# weichen-a-4.net
KiCad netlist of a schematic drawn in EAGLE
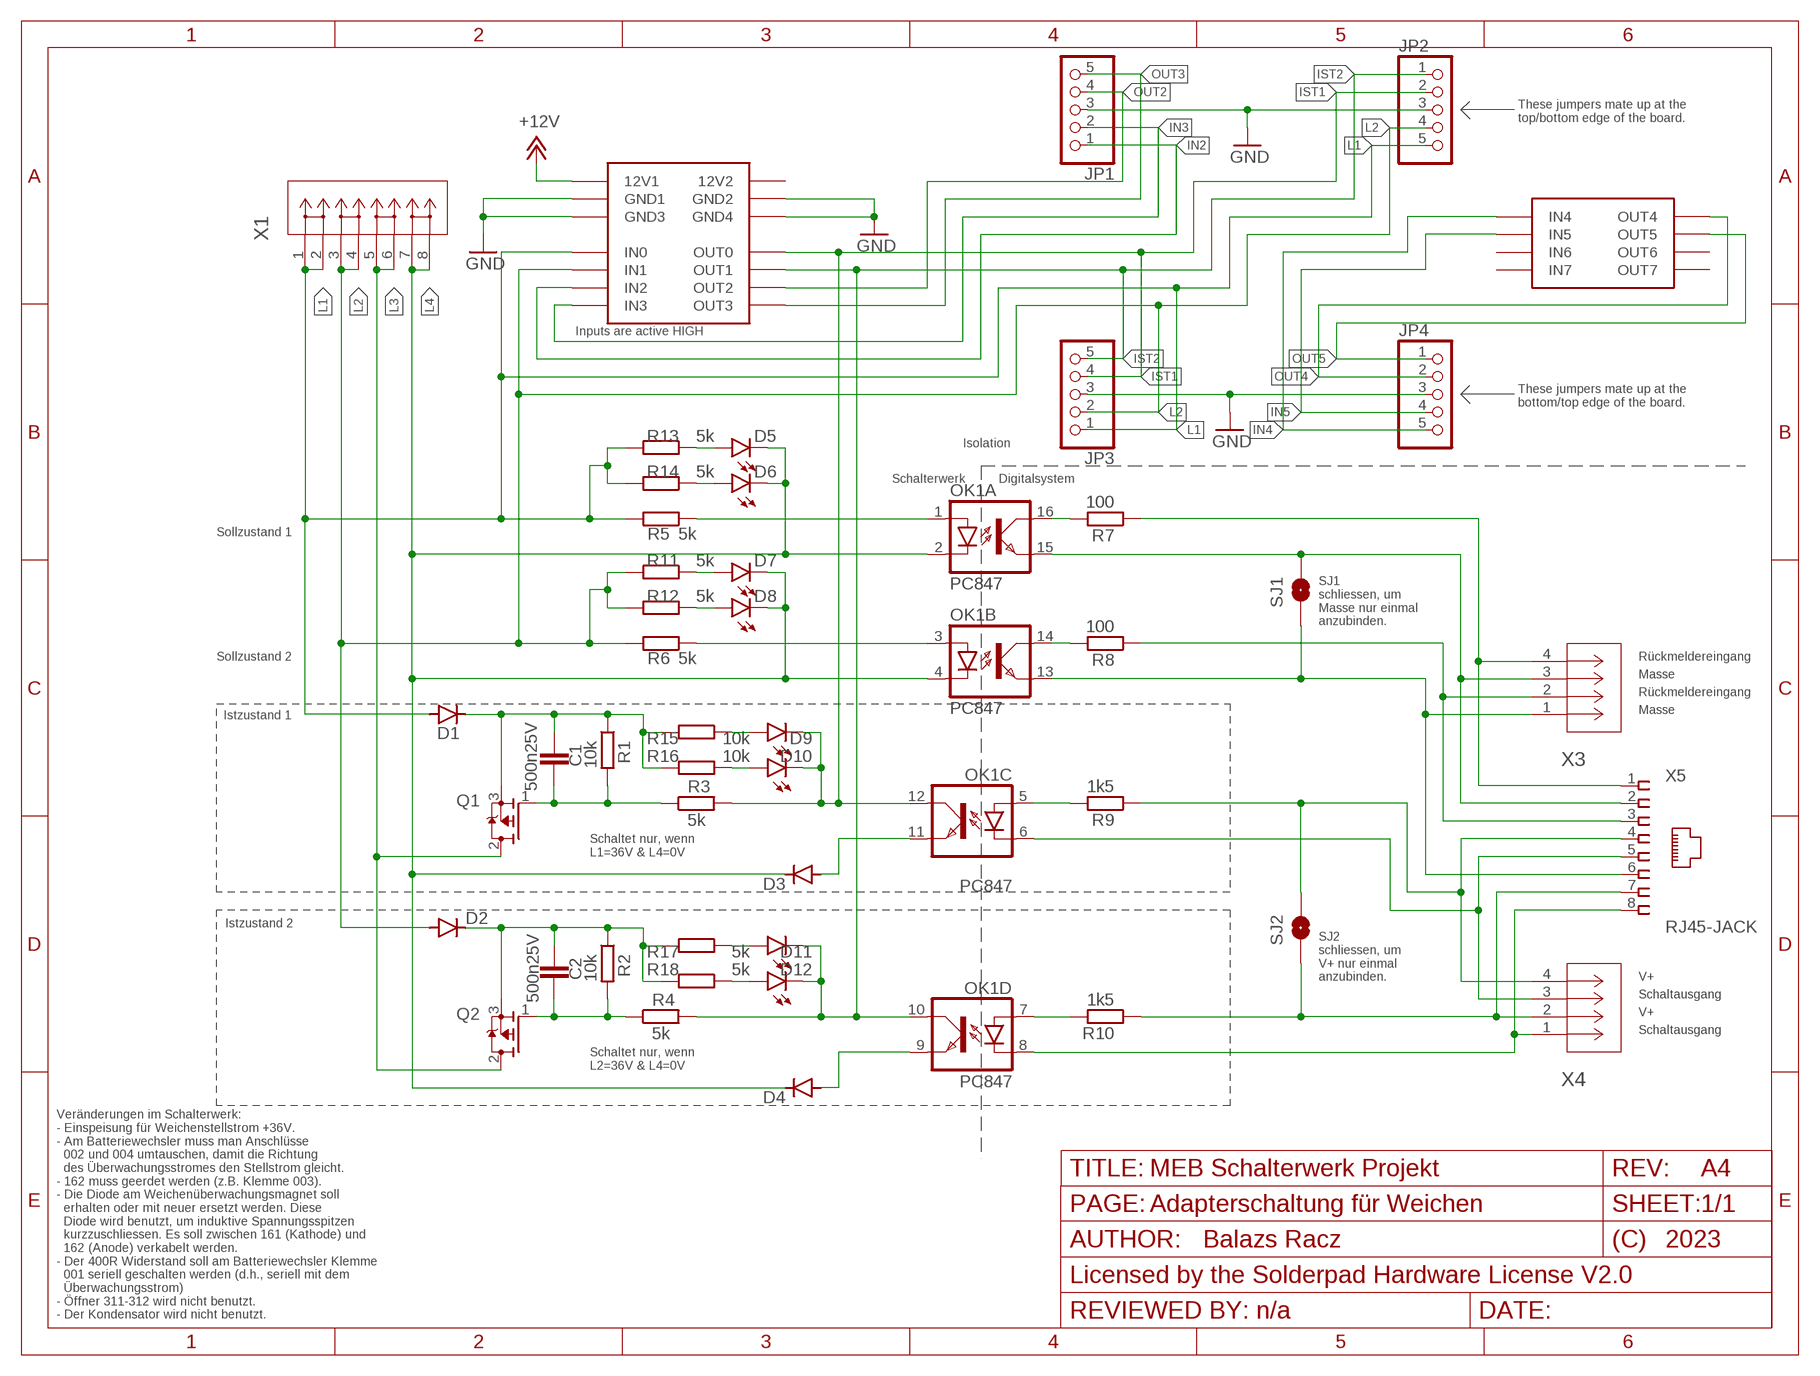
[diagram p0: schematic, sheet 1]

(export (version "E")
  (design (tool "Eeschema 10.0.6"))
  (components
    (comp (ref "C1")
      (value "500n25V")
      (footprint "eagle-import:C0805")
      (libsource (lib "eagle-import") (part "C-EUC0805"))
    )
    (comp (ref "C2")
      (value "500n25V")
      (footprint "eagle-import:C0805")
      (libsource (lib "eagle-import") (part "C-EUC0805"))
    )
    (comp (ref "D1")
      (value "DIODE-DO214AC")
      (footprint "eagle-import:DO214AC")
      (libsource (lib "eagle-import") (part "DIODE-DO214AC"))
    )
    (comp (ref "D2")
      (value "DIODE-DO214AC")
      (footprint "eagle-import:DO214AC")
      (libsource (lib "eagle-import") (part "DIODE-DO214AC"))
    )
    (comp (ref "D3")
      (value "DIODE-MINIMELF")
      (footprint "eagle-import:MINIMELF")
      (libsource (lib "eagle-import") (part "DIODE-MINIMELF"))
    )
    (comp (ref "D4")
      (value "DIODE-MINIMELF")
      (footprint "eagle-import:MINIMELF")
      (libsource (lib "eagle-import") (part "DIODE-MINIMELF"))
    )
    (comp (ref "D5")
      (value "LEDCHIPLED_0603")
      (footprint "eagle-import:CHIPLED_0603")
      (libsource (lib "eagle-import") (part "LEDCHIPLED_0603"))
    )
    (comp (ref "D6")
      (value "LEDHEADER")
      (footprint "eagle-import:LEDHEADER")
      (libsource (lib "eagle-import") (part "LEDHEADER"))
    )
    (comp (ref "D7")
      (value "LEDCHIPLED_0603")
      (footprint "eagle-import:CHIPLED_0603")
      (libsource (lib "eagle-import") (part "LEDCHIPLED_0603"))
    )
    (comp (ref "D8")
      (value "LEDHEADER")
      (footprint "eagle-import:LEDHEADER")
      (libsource (lib "eagle-import") (part "LEDHEADER"))
    )
    (comp (ref "D9")
      (value "LEDCHIPLED_0603")
      (footprint "eagle-import:CHIPLED_0603")
      (libsource (lib "eagle-import") (part "LEDCHIPLED_0603"))
    )
    (comp (ref "D10")
      (value "LEDHEADER")
      (footprint "eagle-import:LEDHEADER")
      (libsource (lib "eagle-import") (part "LEDHEADER"))
    )
    (comp (ref "D11")
      (value "LEDCHIPLED_0603")
      (footprint "eagle-import:CHIPLED_0603")
      (libsource (lib "eagle-import") (part "LEDCHIPLED_0603"))
    )
    (comp (ref "D12")
      (value "LEDHEADER")
      (footprint "eagle-import:LEDHEADER")
      (libsource (lib "eagle-import") (part "LEDHEADER"))
    )
    (comp (ref "JP1")
      (value "PINHD-1X55X2MM")
      (footprint "eagle-import:1_05X2MM")
      (libsource (lib "eagle-import") (part "PINHD-1X55X2MM"))
    )
    (comp (ref "JP2")
      (value "PINHD-1X55X2MM")
      (footprint "eagle-import:1_05X2MM")
      (libsource (lib "eagle-import") (part "PINHD-1X55X2MM"))
    )
    (comp (ref "JP3")
      (value "PINHD-1X55X2MM")
      (footprint "eagle-import:1_05X2MM")
      (libsource (lib "eagle-import") (part "PINHD-1X55X2MM"))
    )
    (comp (ref "JP4")
      (value "PINHD-1X55X2MM")
      (footprint "eagle-import:1_05X2MM")
      (libsource (lib "eagle-import") (part "PINHD-1X55X2MM"))
    )
    (comp (ref "OK1")
      (value "PC847")
      (footprint "eagle-import:DIL16")
      (libsource (lib "eagle-import") (part "PC847"))
    )
    (comp (ref "Q1")
      (value "P-MOSFET")
      (footprint "eagle-import:DPAK-2")
      (fields (field (name "MANUFACTURER") "Infineon"))
      (libsource (lib "eagle-import") (part "P-MOSFET"))
    )
    (comp (ref "Q2")
      (value "P-MOSFET")
      (footprint "eagle-import:DPAK-2")
      (fields (field (name "MANUFACTURER") "Infineon"))
      (libsource (lib "eagle-import") (part "P-MOSFET"))
    )
    (comp (ref "R1")
      (value "10k")
      (footprint "eagle-import:R0805")
      (libsource (lib "eagle-import") (part "R-EU_R0805"))
    )
    (comp (ref "R2")
      (value "10k")
      (footprint "eagle-import:R0805")
      (libsource (lib "eagle-import") (part "R-EU_R0805"))
    )
    (comp (ref "R3")
      (value "5k")
      (footprint "eagle-import:R0805")
      (libsource (lib "eagle-import") (part "R-EU_R0805"))
    )
    (comp (ref "R4")
      (value "5k")
      (footprint "eagle-import:R0805")
      (libsource (lib "eagle-import") (part "R-EU_R0805"))
    )
    (comp (ref "R5")
      (value "5k")
      (footprint "eagle-import:R0805")
      (libsource (lib "eagle-import") (part "R-EU_R0805"))
    )
    (comp (ref "R6")
      (value "5k")
      (footprint "eagle-import:R0805")
      (libsource (lib "eagle-import") (part "R-EU_R0805"))
    )
    (comp (ref "R7")
      (value "100")
      (footprint "eagle-import:R0805")
      (libsource (lib "eagle-import") (part "R-EU_R0805"))
    )
    (comp (ref "R8")
      (value "100")
      (footprint "eagle-import:R0805")
      (libsource (lib "eagle-import") (part "R-EU_R0805"))
    )
    (comp (ref "R9")
      (value "1k5")
      (footprint "eagle-import:R0805")
      (libsource (lib "eagle-import") (part "R-EU_R0805"))
    )
    (comp (ref "R10")
      (value "1k5")
      (footprint "eagle-import:R0805")
      (libsource (lib "eagle-import") (part "R-EU_R0805"))
    )
    (comp (ref "R11")
      (value "5k")
      (footprint "eagle-import:R0805")
      (libsource (lib "eagle-import") (part "R-EU_R0805"))
    )
    (comp (ref "R12")
      (value "5k")
      (footprint "eagle-import:R0805")
      (libsource (lib "eagle-import") (part "R-EU_R0805"))
    )
    (comp (ref "R13")
      (value "5k")
      (footprint "eagle-import:R0805")
      (libsource (lib "eagle-import") (part "R-EU_R0805"))
    )
    (comp (ref "R14")
      (value "5k")
      (footprint "eagle-import:R0805")
      (libsource (lib "eagle-import") (part "R-EU_R0805"))
    )
    (comp (ref "R15")
      (value "10k")
      (footprint "eagle-import:R0805")
      (libsource (lib "eagle-import") (part "R-EU_R0805"))
    )
    (comp (ref "R16")
      (value "10k")
      (footprint "eagle-import:R0805")
      (libsource (lib "eagle-import") (part "R-EU_R0805"))
    )
    (comp (ref "R17")
      (value "5k")
      (footprint "eagle-import:R0805")
      (libsource (lib "eagle-import") (part "R-EU_R0805"))
    )
    (comp (ref "R18")
      (value "5k")
      (footprint "eagle-import:R0805")
      (libsource (lib "eagle-import") (part "R-EU_R0805"))
    )
    (comp (ref "SJ1")
      (value "SJRND2")
      (footprint "eagle-import:SJ_RND2")
      (libsource (lib "eagle-import") (part "SJRND2"))
    )
    (comp (ref "SJ2")
      (value "SJRND2")
      (footprint "eagle-import:SJ_RND2")
      (libsource (lib "eagle-import") (part "SJRND2"))
    )
    (comp (ref "X1")
      (value "PHNX_4P_508CONN_1017493")
      (footprint "eagle-import:PHNX_4P_508")
      (fields
        (field (name "MANUFACTURER_PART_NUMBER") "1017505")
        (field (name "COPYRIGHT") "Copyright (C) 2023 Ultra Librarian. All rights reserved.")
      )
      (libsource (lib "eagle-import") (part "PHNX_4P_508CONN_1017493"))
    )
    (comp (ref "X2")
      (value "IO-HAT")
      (footprint "eagle-import:IOBOARD")
      (libsource (lib "eagle-import") (part "IO-HAT"))
    )
    (comp (ref "X3")
      (value "PHNX_4P_350CONN_1984989_PXC")
      (footprint "eagle-import:PHNX_4P_350")
      (fields
        (field (name "MANUFACTURER_PART_NUMBER") "1984989")
        (field (name "COPYRIGHT") "Copyright (C) 2023 Ultra Librarian. All rights reserved.")
      )
      (libsource (lib "eagle-import") (part "PHNX_4P_350CONN_1984989_PXC"))
    )
    (comp (ref "X4")
      (value "PHNX_4P_350CONN_1984989_PXC")
      (footprint "eagle-import:PHNX_4P_350")
      (fields
        (field (name "MANUFACTURER_PART_NUMBER") "1984989")
        (field (name "COPYRIGHT") "Copyright (C) 2023 Ultra Librarian. All rights reserved.")
      )
      (libsource (lib "eagle-import") (part "PHNX_4P_350CONN_1984989_PXC"))
    )
    (comp (ref "X5")
      (value "RJ45-JACK")
      (footprint "eagle-import:RJ45-PULSE-E5J88")
      (libsource (lib "eagle-import") (part "RJ45-JACKRJ45-PULSE-E5J00"))
    )
  )
  (nets
    (net (code "1") (name "+12V") (class "Default")
      (node (ref "X2") (pin "P$1") (pinfunction "12V1_P$1") (pintype "power_in"))
    )
    (net (code "2") (name "/12V2") (class "Default")
      (node (ref "X2") (pin "P$22") (pinfunction "12V2_P$22") (pintype "power_in"))
    )
    (net (code "3") (name "GND") (class "Default")
      (node (ref "JP1") (pin "3") (pinfunction "3_3") (pintype "passive"))
      (node (ref "JP2") (pin "3") (pinfunction "3_3") (pintype "passive"))
      (node (ref "JP3") (pin "3") (pinfunction "3_3") (pintype "passive"))
      (node (ref "JP4") (pin "3") (pinfunction "3_3") (pintype "passive"))
      (node (ref "X2") (pin "P$11") (pinfunction "GND3_P$11") (pintype "power_in"))
      (node (ref "X2") (pin "P$12") (pinfunction "GND4_P$12") (pintype "power_in"))
      (node (ref "X2") (pin "P$2") (pinfunction "GND1_P$2") (pintype "power_in"))
      (node (ref "X2") (pin "P$21") (pinfunction "GND2_P$21") (pintype "power_in"))
    )
    (net (code "4") (name "IN2") (class "Default")
      (node (ref "JP1") (pin "1") (pinfunction "1_1") (pintype "passive"))
      (node (ref "X2") (pin "P$5") (pinfunction "IN2_P$5") (pintype "input"))
    )
    (net (code "5") (name "IN3") (class "Default")
      (node (ref "JP1") (pin "2") (pinfunction "2_2") (pintype "passive"))
      (node (ref "X2") (pin "P$6") (pinfunction "IN3_P$6") (pintype "input"))
    )
    (net (code "6") (name "IN4") (class "Default")
      (node (ref "JP4") (pin "5") (pinfunction "5_5") (pintype "passive"))
      (node (ref "X2") (pin "P$7") (pinfunction "IN4_P$7") (pintype "input"))
    )
    (net (code "7") (name "IN5") (class "Default")
      (node (ref "JP4") (pin "4") (pinfunction "4_4") (pintype "passive"))
      (node (ref "X2") (pin "P$8") (pinfunction "IN5_P$8") (pintype "input"))
    )
    (net (code "8") (name "IST1") (class "Default")
      (node (ref "D10") (pin "C") (pinfunction "C_C") (pintype "passive"))
      (node (ref "D9") (pin "C") (pinfunction "C_C") (pintype "passive"))
      (node (ref "JP2") (pin "2") (pinfunction "2_2") (pintype "passive"))
      (node (ref "JP3") (pin "4") (pinfunction "4_4") (pintype "passive"))
      (node (ref "OK1") (pin "12") (pinfunction "COL_12") (pintype "passive"))
      (node (ref "R3") (pin "2") (pinfunction "2_2") (pintype "passive"))
      (node (ref "X2") (pin "P$20") (pinfunction "OUT0_P$20") (pintype "open_collector"))
    )
    (net (code "9") (name "IST2") (class "Default")
      (node (ref "D11") (pin "C") (pinfunction "C_C") (pintype "passive"))
      (node (ref "D12") (pin "C") (pinfunction "C_C") (pintype "passive"))
      (node (ref "JP2") (pin "1") (pinfunction "1_1") (pintype "passive"))
      (node (ref "JP3") (pin "5") (pinfunction "5_5") (pintype "passive"))
      (node (ref "OK1") (pin "10") (pinfunction "COL_10") (pintype "passive"))
      (node (ref "R4") (pin "2") (pinfunction "2_2") (pintype "passive"))
      (node (ref "X2") (pin "P$19") (pinfunction "OUT1_P$19") (pintype "open_collector"))
    )
    (net (code "10") (name "L1") (class "Default")
      (node (ref "D1") (pin "A") (pinfunction "A_A") (pintype "passive"))
      (node (ref "JP2") (pin "5") (pinfunction "5_5") (pintype "passive"))
      (node (ref "JP3") (pin "1") (pinfunction "1_1") (pintype "passive"))
      (node (ref "R13") (pin "2") (pinfunction "2_2") (pintype "passive"))
      (node (ref "R14") (pin "2") (pinfunction "2_2") (pintype "passive"))
      (node (ref "R5") (pin "2") (pinfunction "2_2") (pintype "passive"))
      (node (ref "X1") (pin "1") (pinfunction "1_1") (pintype "passive"))
      (node (ref "X1") (pin "2") (pinfunction "2_2") (pintype "passive"))
      (node (ref "X2") (pin "P$3") (pinfunction "IN0_P$3") (pintype "input"))
    )
    (net (code "11") (name "L2") (class "Default")
      (node (ref "D2") (pin "A") (pinfunction "A_A") (pintype "passive"))
      (node (ref "JP2") (pin "4") (pinfunction "4_4") (pintype "passive"))
      (node (ref "JP3") (pin "2") (pinfunction "2_2") (pintype "passive"))
      (node (ref "R11") (pin "2") (pinfunction "2_2") (pintype "passive"))
      (node (ref "R12") (pin "2") (pinfunction "2_2") (pintype "passive"))
      (node (ref "R6") (pin "2") (pinfunction "2_2") (pintype "passive"))
      (node (ref "X1") (pin "3") (pinfunction "3_3") (pintype "passive"))
      (node (ref "X1") (pin "4") (pinfunction "4_4") (pintype "passive"))
      (node (ref "X2") (pin "P$4") (pinfunction "IN1_P$4") (pintype "input"))
    )
    (net (code "12") (name "L3") (class "Default")
      (node (ref "Q1") (pin "2") (pinfunction "D_2") (pintype "passive"))
      (node (ref "Q2") (pin "2") (pinfunction "D_2") (pintype "passive"))
      (node (ref "X1") (pin "5") (pinfunction "5_5") (pintype "passive"))
      (node (ref "X1") (pin "6") (pinfunction "6_6") (pintype "passive"))
    )
    (net (code "13") (name "L4") (class "Default")
      (node (ref "D3") (pin "C") (pinfunction "C_C") (pintype "passive"))
      (node (ref "D4") (pin "C") (pinfunction "C_C") (pintype "passive"))
      (node (ref "D5") (pin "C") (pinfunction "C_C") (pintype "passive"))
      (node (ref "D6") (pin "C") (pinfunction "C_C") (pintype "passive"))
      (node (ref "D7") (pin "C") (pinfunction "C_C") (pintype "passive"))
      (node (ref "D8") (pin "C") (pinfunction "C_C") (pintype "passive"))
      (node (ref "OK1") (pin "2") (pinfunction "C_2") (pintype "passive"))
      (node (ref "OK1") (pin "4") (pinfunction "C_4") (pintype "passive"))
      (node (ref "X1") (pin "7") (pinfunction "7_7") (pintype "passive"))
      (node (ref "X1") (pin "8") (pinfunction "8_8") (pintype "passive"))
    )
    (net (code "14") (name "Net-(D5-PadA)") (class "Default")
      (node (ref "D5") (pin "A") (pinfunction "A_A") (pintype "passive"))
      (node (ref "R13") (pin "1") (pinfunction "1_1") (pintype "passive"))
    )
    (net (code "15") (name "Net-(D6-PadA)") (class "Default")
      (node (ref "D6") (pin "A") (pinfunction "A_A") (pintype "passive"))
      (node (ref "R14") (pin "1") (pinfunction "1_1") (pintype "passive"))
    )
    (net (code "16") (name "Net-(D7-PadA)") (class "Default")
      (node (ref "D7") (pin "A") (pinfunction "A_A") (pintype "passive"))
      (node (ref "R11") (pin "1") (pinfunction "1_1") (pintype "passive"))
    )
    (net (code "17") (name "Net-(D8-PadA)") (class "Default")
      (node (ref "D8") (pin "A") (pinfunction "A_A") (pintype "passive"))
      (node (ref "R12") (pin "1") (pinfunction "1_1") (pintype "passive"))
    )
    (net (code "18") (name "Net-(D9-PadA)") (class "Default")
      (node (ref "D9") (pin "A") (pinfunction "A_A") (pintype "passive"))
      (node (ref "R15") (pin "1") (pinfunction "1_1") (pintype "passive"))
    )
    (net (code "19") (name "Net-(D10-PadA)") (class "Default")
      (node (ref "D10") (pin "A") (pinfunction "A_A") (pintype "passive"))
      (node (ref "R16") (pin "1") (pinfunction "1_1") (pintype "passive"))
    )
    (net (code "20") (name "Net-(D11-PadA)") (class "Default")
      (node (ref "D11") (pin "A") (pinfunction "A_A") (pintype "passive"))
      (node (ref "R17") (pin "1") (pinfunction "1_1") (pintype "passive"))
    )
    (net (code "21") (name "Net-(D12-PadA)") (class "Default")
      (node (ref "D12") (pin "A") (pinfunction "A_A") (pintype "passive"))
      (node (ref "R18") (pin "1") (pinfunction "1_1") (pintype "passive"))
    )
    (net (code "22") (name "Net-(OK1A-A)") (class "Default")
      (node (ref "OK1") (pin "1") (pinfunction "A_1") (pintype "passive"))
      (node (ref "R5") (pin "1") (pinfunction "1_1") (pintype "passive"))
    )
    (net (code "23") (name "Net-(OK1A-COL)") (class "Default")
      (node (ref "OK1") (pin "16") (pinfunction "COL_16") (pintype "passive"))
      (node (ref "R7") (pin "2") (pinfunction "2_2") (pintype "passive"))
    )
    (net (code "24") (name "Net-(OK1A-EMIT)") (class "Default")
      (node (ref "OK1") (pin "15") (pinfunction "EMIT_15") (pintype "passive"))
      (node (ref "SJ1") (pin "P$2") (pinfunction "2_P$2") (pintype "passive"))
      (node (ref "X3") (pin "3") (pinfunction "3_3") (pintype "passive"))
      (node (ref "X5") (pin "2") (pinfunction "2_2") (pintype "passive"))
    )
    (net (code "25") (name "Net-(OK1B-A)") (class "Default")
      (node (ref "OK1") (pin "3") (pinfunction "A_3") (pintype "passive"))
      (node (ref "R6") (pin "1") (pinfunction "1_1") (pintype "passive"))
    )
    (net (code "26") (name "Net-(OK1B-COL)") (class "Default")
      (node (ref "OK1") (pin "14") (pinfunction "COL_14") (pintype "passive"))
      (node (ref "R8") (pin "2") (pinfunction "2_2") (pintype "passive"))
    )
    (net (code "27") (name "Net-(OK1B-EMIT)") (class "Default")
      (node (ref "OK1") (pin "13") (pinfunction "EMIT_13") (pintype "passive"))
      (node (ref "SJ1") (pin "P$1") (pinfunction "1_P$1") (pintype "passive"))
      (node (ref "X3") (pin "1") (pinfunction "1_1") (pintype "passive"))
      (node (ref "X5") (pin "6") (pinfunction "6_6") (pintype "passive"))
    )
    (net (code "28") (name "Net-(OK1C-A)") (class "Default")
      (node (ref "OK1") (pin "5") (pinfunction "A_5") (pintype "passive"))
      (node (ref "R9") (pin "2") (pinfunction "2_2") (pintype "passive"))
    )
    (net (code "29") (name "Net-(OK1C-C)") (class "Default")
      (node (ref "OK1") (pin "6") (pinfunction "C_6") (pintype "passive"))
      (node (ref "X4") (pin "3") (pinfunction "3_3") (pintype "passive"))
      (node (ref "X5") (pin "5") (pinfunction "5_5") (pintype "passive"))
    )
    (net (code "30") (name "Net-(OK1C-EMIT)") (class "Default")
      (node (ref "D3") (pin "A") (pinfunction "A_A") (pintype "passive"))
      (node (ref "OK1") (pin "11") (pinfunction "EMIT_11") (pintype "passive"))
    )
    (net (code "31") (name "Net-(OK1D-A)") (class "Default")
      (node (ref "OK1") (pin "7") (pinfunction "A_7") (pintype "passive"))
      (node (ref "R10") (pin "2") (pinfunction "2_2") (pintype "passive"))
    )
    (net (code "32") (name "Net-(OK1D-C)") (class "Default")
      (node (ref "OK1") (pin "8") (pinfunction "C_8") (pintype "passive"))
      (node (ref "X4") (pin "1") (pinfunction "1_1") (pintype "passive"))
      (node (ref "X5") (pin "8") (pinfunction "8_8") (pintype "passive"))
    )
    (net (code "33") (name "Net-(OK1D-EMIT)") (class "Default")
      (node (ref "D4") (pin "A") (pinfunction "A_A") (pintype "passive"))
      (node (ref "OK1") (pin "9") (pinfunction "EMIT_9") (pintype "passive"))
    )
    (net (code "34") (name "Net-(Q1-G)") (class "Default")
      (node (ref "C1") (pin "2") (pinfunction "2_2") (pintype "passive"))
      (node (ref "Q1") (pin "1") (pinfunction "G_1") (pintype "passive"))
      (node (ref "R1") (pin "2") (pinfunction "2_2") (pintype "passive"))
      (node (ref "R3") (pin "1") (pinfunction "1_1") (pintype "passive"))
    )
    (net (code "35") (name "Net-(Q1-S)") (class "Default")
      (node (ref "C1") (pin "1") (pinfunction "1_1") (pintype "passive"))
      (node (ref "D1") (pin "C") (pinfunction "C_C") (pintype "passive"))
      (node (ref "Q1") (pin "3") (pinfunction "S_3") (pintype "passive"))
      (node (ref "R1") (pin "1") (pinfunction "1_1") (pintype "passive"))
      (node (ref "R15") (pin "2") (pinfunction "2_2") (pintype "passive"))
      (node (ref "R16") (pin "2") (pinfunction "2_2") (pintype "passive"))
    )
    (net (code "36") (name "Net-(Q2-G)") (class "Default")
      (node (ref "C2") (pin "2") (pinfunction "2_2") (pintype "passive"))
      (node (ref "Q2") (pin "1") (pinfunction "G_1") (pintype "passive"))
      (node (ref "R2") (pin "2") (pinfunction "2_2") (pintype "passive"))
      (node (ref "R4") (pin "1") (pinfunction "1_1") (pintype "passive"))
    )
    (net (code "37") (name "Net-(Q2-S)") (class "Default")
      (node (ref "C2") (pin "1") (pinfunction "1_1") (pintype "passive"))
      (node (ref "D2") (pin "C") (pinfunction "C_C") (pintype "passive"))
      (node (ref "Q2") (pin "3") (pinfunction "S_3") (pintype "passive"))
      (node (ref "R17") (pin "2") (pinfunction "2_2") (pintype "passive"))
      (node (ref "R18") (pin "2") (pinfunction "2_2") (pintype "passive"))
      (node (ref "R2") (pin "1") (pinfunction "1_1") (pintype "passive"))
    )
    (net (code "38") (name "Net-(R7-Pad1)") (class "Default")
      (node (ref "R7") (pin "1") (pinfunction "1_1") (pintype "passive"))
      (node (ref "X3") (pin "4") (pinfunction "4_4") (pintype "passive"))
      (node (ref "X5") (pin "1") (pinfunction "1_1") (pintype "passive"))
    )
    (net (code "39") (name "Net-(R8-Pad1)") (class "Default")
      (node (ref "R8") (pin "1") (pinfunction "1_1") (pintype "passive"))
      (node (ref "X3") (pin "2") (pinfunction "2_2") (pintype "passive"))
      (node (ref "X5") (pin "3") (pinfunction "3_3") (pintype "passive"))
    )
    (net (code "40") (name "Net-(SJ2-1)") (class "Default")
      (node (ref "R10") (pin "1") (pinfunction "1_1") (pintype "passive"))
      (node (ref "SJ2") (pin "P$1") (pinfunction "1_P$1") (pintype "passive"))
      (node (ref "X4") (pin "2") (pinfunction "2_2") (pintype "passive"))
      (node (ref "X5") (pin "7") (pinfunction "7_7") (pintype "passive"))
    )
    (net (code "41") (name "Net-(SJ2-2)") (class "Default")
      (node (ref "R9") (pin "1") (pinfunction "1_1") (pintype "passive"))
      (node (ref "SJ2") (pin "P$2") (pinfunction "2_P$2") (pintype "passive"))
      (node (ref "X4") (pin "4") (pinfunction "4_4") (pintype "passive"))
      (node (ref "X5") (pin "4") (pinfunction "4_4") (pintype "passive"))
    )
    (net (code "42") (name "OUT2") (class "Default")
      (node (ref "JP1") (pin "4") (pinfunction "4_4") (pintype "passive"))
      (node (ref "X2") (pin "P$18") (pinfunction "OUT2_P$18") (pintype "open_collector"))
    )
    (net (code "43") (name "OUT3") (class "Default")
      (node (ref "JP1") (pin "5") (pinfunction "5_5") (pintype "passive"))
      (node (ref "X2") (pin "P$17") (pinfunction "OUT3_P$17") (pintype "open_collector"))
    )
    (net (code "44") (name "OUT4") (class "Default")
      (node (ref "JP4") (pin "2") (pinfunction "2_2") (pintype "passive"))
      (node (ref "X2") (pin "P$16") (pinfunction "OUT4_P$16") (pintype "open_collector"))
    )
    (net (code "45") (name "OUT5") (class "Default")
      (node (ref "JP4") (pin "1") (pinfunction "1_1") (pintype "passive"))
      (node (ref "X2") (pin "P$15") (pinfunction "OUT5_P$15") (pintype "open_collector"))
    )
    (net (code "46") (name "unconnected-(X2B-IN6-PadP$9)") (class "Default")
      (node (ref "X2") (pin "P$9") (pinfunction "IN6_P$9") (pintype "input"))
    )
    (net (code "47") (name "unconnected-(X2B-IN7-PadP$10)") (class "Default")
      (node (ref "X2") (pin "P$10") (pinfunction "IN7_P$10") (pintype "input"))
    )
    (net (code "48") (name "unconnected-(X2B-OUT6-PadP$14)") (class "Default")
      (node (ref "X2") (pin "P$14") (pinfunction "OUT6_P$14") (pintype "open_collector"))
    )
    (net (code "49") (name "unconnected-(X2B-OUT7-PadP$13)") (class "Default")
      (node (ref "X2") (pin "P$13") (pinfunction "OUT7_P$13") (pintype "open_collector"))
    )
  )
)
